# Lcd_CapTouch.net
KiCad netlist of a schematic drawn in Altium Designer
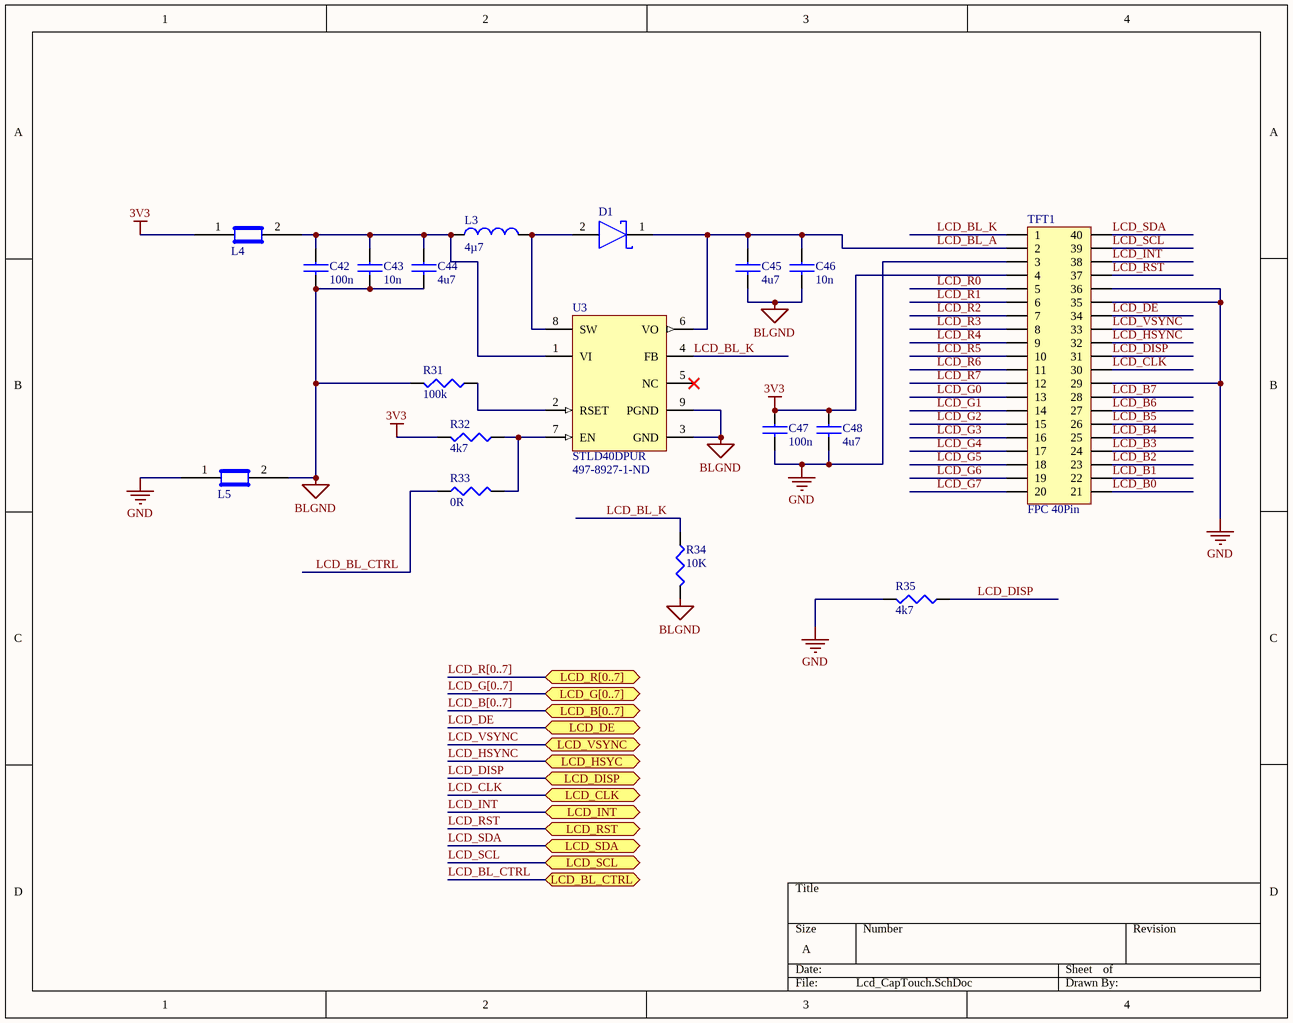
[diagram p0: Lcd_CapTouch.SchDoc]

(export (version "E")
  (design (tool "Eeschema 10.0.6"))
  (components
    (comp (ref "C42")
      (value "100n")
      (footprint "C0402")
      (description "CAP CER .10UF 50V X5R 10% 0402")
      (fields
        (field (name "MANUFACTURER") "TDK Corporation")
        (field (name "MANUFACTURER PART NUMBER") "C1005X5R1H104K")
      )
      (libsource (lib "iMX6_Rex_Development_Baseboard_V1I1") (part "C1005X5R1H104K"))
    )
    (comp (ref "C43")
      (value "10n")
      (footprint "C0402")
      (description "CAP CER 10000PF 16V X7R 10% 0402")
      (fields
        (field (name "MANUFACTURER") "TDK Corporation")
        (field (name "MANUFACTURER PART NUMBER") "C1005X7R1C103K")
      )
      (libsource (lib "iMX6_Rex_Development_Baseboard_V1I1") (part "C1005X7R1C103K"))
    )
    (comp (ref "C44")
      (value "4u7")
      (footprint "C0402")
      (description "CAP CER 4.7UF 10V 20% X5R 0402")
      (fields
        (field (name "MANUFACTURER") "TDK Corporation")
        (field (name "MANUFACTURER PART NUMBER") "C1005X5R1A475M")
        (field (name ".CHECKED PCB") "RF")
        (field (name ".CHECKED SCH") "RF")
      )
      (libsource (lib "iMX6_Rex_Development_Baseboard_V1I1") (part "C1005X5R1A475M"))
    )
    (comp (ref "C45")
      (value "4u7")
      (footprint "C0402")
      (description "CAP CER 4.7UF 10V 20% X5R 0402")
      (fields
        (field (name "MANUFACTURER") "TDK Corporation")
        (field (name "MANUFACTURER PART NUMBER") "C1005X5R1A475M")
        (field (name ".CHECKED PCB") "RF")
        (field (name ".CHECKED SCH") "RF")
      )
      (libsource (lib "iMX6_Rex_Development_Baseboard_V1I1") (part "C1005X5R1A475M"))
    )
    (comp (ref "C46")
      (value "10n")
      (footprint "C0402")
      (description "CAP CER 10000PF 16V X7R 10% 0402")
      (fields
        (field (name "MANUFACTURER") "TDK Corporation")
        (field (name "MANUFACTURER PART NUMBER") "C1005X7R1C103K")
      )
      (libsource (lib "iMX6_Rex_Development_Baseboard_V1I1") (part "C1005X7R1C103K"))
    )
    (comp (ref "C47")
      (value "100n")
      (footprint "C0402")
      (description "CAP CER .10UF 50V X5R 10% 0402")
      (fields
        (field (name "MANUFACTURER") "TDK Corporation")
        (field (name "MANUFACTURER PART NUMBER") "C1005X5R1H104K")
      )
      (libsource (lib "iMX6_Rex_Development_Baseboard_V1I1") (part "C1005X5R1H104K"))
    )
    (comp (ref "C48")
      (value "4u7")
      (footprint "C0402")
      (description "CAP CER 4.7UF 10V 20% X5R 0402")
      (fields
        (field (name "MANUFACTURER") "TDK Corporation")
        (field (name "MANUFACTURER PART NUMBER") "C1005X5R1A475M")
        (field (name ".CHECKED PCB") "RF")
        (field (name ".CHECKED SCH") "RF")
      )
      (libsource (lib "iMX6_Rex_Development_Baseboard_V1I1") (part "C1005X5R1A475M"))
    )
    (comp (ref "D1")
      (value "STPS1L40M")
      (footprint "STPS1L40M")
      (libsource (lib "STLD40DPUR") (part "STPS1L40M"))
    )
    (comp (ref "L3")
      (value "4µ7")
      (footprint "IHLP_255MILx270MIL")
      (description "INDUCTOR POWER 4.7UH 5.5A SMD")
      (fields
        (field (name "MANUFACTURER") "Vishay/Dale")
        (field (name "MANUFACTURER PART NUMBER") "IHLP2525CZER4R7M01")
      )
      (libsource (lib "iMX6_Rex_Development_Baseboard_V1I1") (part "IHLP2525CZER4R7M01"))
    )
    (comp (ref "L4")
      (value "MPZ1608S601A 600OHM/1A")
      (footprint "C0603")
      (description "FERRITE CHIP BEAD 600 OHM SMD 1A")
      (fields
        (field (name "MANUFACTURER") "TDK Corporation")
        (field (name "MANUFACTURER PART NUMBER") "MPZ1608S601A")
        (field (name ".CHECKED PCB") "RF")
        (field (name ".CHECKED SCH") "RF")
      )
      (libsource (lib "iMX6_Rex_Development_Baseboard_V1I1") (part "MPZ1608S601A"))
    )
    (comp (ref "L5")
      (value "MPZ1608S601A 600OHM/1A")
      (footprint "C0603")
      (description "FERRITE CHIP BEAD 600 OHM SMD 1A")
      (fields
        (field (name "MANUFACTURER") "TDK Corporation")
        (field (name "MANUFACTURER PART NUMBER") "MPZ1608S601A")
        (field (name ".CHECKED PCB") "RF")
        (field (name ".CHECKED SCH") "RF")
      )
      (libsource (lib "iMX6_Rex_Development_Baseboard_V1I1") (part "MPZ1608S601A"))
    )
    (comp (ref "R31")
      (value "100k")
      (footprint "R0402")
      (description "RES 10.0K OHM 1/16W 1% 0402 SMD")
      (fields
        (field (name "MANUFACTURER") "Yageo")
        (field (name "MANUFACTURER PART NUMBER") "RC0402FR-0710KL")
      )
      (libsource (lib "iMX6_Rex_Development_Baseboard_V1I1") (part "RC0402FR-0710KL"))
    )
    (comp (ref "R32")
      (value "4k7")
      (footprint "R0402")
      (description "RES 10.0K OHM 1/16W 1% 0402 SMD")
      (fields
        (field (name "MANUFACTURER") "Yageo")
        (field (name "MANUFACTURER PART NUMBER") "RC0402FR-0710KL")
      )
      (libsource (lib "iMX6_Rex_Development_Baseboard_V1I1") (part "RC0402FR-0710KL"))
    )
    (comp (ref "R33")
      (value "0R")
      (footprint "R0402")
      (description "RES 330 OHM 1/16W 1% 0402 SMD")
      (fields
        (field (name "MANUFACTURER") "Vishay Dale")
        (field (name "MANUFACTURER PART NUMBER") "CRCW0402330RFKED")
        (field (name ".CHECKED PCB") "RF")
        (field (name ".CHECKED SCH") "RF")
      )
      (libsource (lib "iMX6_Rex_Development_Baseboard_V1I1") (part "CRCW0402330RFKED"))
    )
    (comp (ref "R34")
      (value "10K")
      (footprint "R0402")
      (description "RES 100 OHM 1/16W 1% 0402 SMD")
      (fields
        (field (name "MANUFACTURER") "Yageo")
        (field (name "MANUFACTURER PART NUMBER") "RC0402FR-07100RL")
        (field (name ".CHECKED PCB") "RF")
        (field (name ".CHECKED SCH") "RF")
      )
      (libsource (lib "iMX6_Rex_Development_Baseboard_V1I1") (part "RC0402FR-07100RL"))
    )
    (comp (ref "R35")
      (value "4k7")
      (footprint "R0402")
      (description "RES 10.0K OHM 1/16W 1% 0402 SMD")
      (fields
        (field (name "MANUFACTURER") "Yageo")
        (field (name "MANUFACTURER PART NUMBER") "RC0402FR-0710KL")
      )
      (libsource (lib "iMX6_Rex_Development_Baseboard_V1I1") (part "RC0402FR-0710KL"))
    )
    (comp (ref "TFT1") (value "FPC 40Pin") (footprint "FPC_40Pin") (libsource (lib "L1") (part "FPC_40Pin")))
    (comp (ref "U3")
      (value "STLD40DPUR")
      (footprint "QFN8_V")
      (description "White Led Power Supply For Large Display Backlight, 8-Pin VFDFPN, Tape and Reel")
      (fields (field (name "SUPPLIER PART NUMBER 1") "497-8927-1-ND"))
      (libsource (lib "STLD40DPUR") (part "STLD40DPUR"))
    )
  )
  (nets
    (net (code "1") (name "/LCD_B0") (class "Default")
      (node (ref "TFT1") (pin "21") (pinfunction "21_21") (pintype "passive"))
    )
    (net (code "2") (name "/LCD_B1") (class "Default")
      (node (ref "TFT1") (pin "22") (pinfunction "22_22") (pintype "passive"))
    )
    (net (code "3") (name "/LCD_B2") (class "Default")
      (node (ref "TFT1") (pin "23") (pinfunction "23_23") (pintype "passive"))
    )
    (net (code "4") (name "/LCD_B3") (class "Default")
      (node (ref "TFT1") (pin "24") (pinfunction "24_24") (pintype "passive"))
    )
    (net (code "5") (name "/LCD_B4") (class "Default")
      (node (ref "TFT1") (pin "25") (pinfunction "25_25") (pintype "passive"))
    )
    (net (code "6") (name "/LCD_B5") (class "Default")
      (node (ref "TFT1") (pin "26") (pinfunction "26_26") (pintype "passive"))
    )
    (net (code "7") (name "/LCD_B6") (class "Default")
      (node (ref "TFT1") (pin "27") (pinfunction "27_27") (pintype "passive"))
    )
    (net (code "8") (name "/LCD_B7") (class "Default")
      (node (ref "TFT1") (pin "28") (pinfunction "28_28") (pintype "passive"))
    )
    (net (code "9") (name "/LCD_BL_A") (class "Default")
      (node (ref "C45") (pin "1") (pinfunction "1_1") (pintype "passive"))
      (node (ref "C46") (pin "1") (pinfunction "1_1") (pintype "passive"))
      (node (ref "D1") (pin "1") (pinfunction "K_1") (pintype "passive"))
      (node (ref "TFT1") (pin "2") (pinfunction "2_2") (pintype "passive"))
      (node (ref "U3") (pin "6") (pinfunction "VO_6") (pintype "output"))
    )
    (net (code "10") (name "/LCD_BL_CTRL") (class "Default")
      (node (ref "R33") (pin "1") (pinfunction "1_1") (pintype "passive"))
    )
    (net (code "11") (name "/LCD_BL_K") (class "Default")
      (node (ref "R34") (pin "1") (pinfunction "1_1") (pintype "passive"))
      (node (ref "TFT1") (pin "1") (pinfunction "1_1") (pintype "passive"))
      (node (ref "U3") (pin "4") (pinfunction "FB_4") (pintype "passive"))
    )
    (net (code "13") (name "/LCD_CLK") (class "Default")
      (node (ref "TFT1") (pin "30") (pinfunction "30_30") (pintype "passive"))
    )
    (net (code "14") (name "/LCD_DE") (class "Default")
      (node (ref "TFT1") (pin "34") (pinfunction "34_34") (pintype "passive"))
    )
    (net (code "15") (name "/LCD_DISP") (class "Default")
      (node (ref "R35") (pin "1") (pinfunction "1_1") (pintype "passive"))
      (node (ref "TFT1") (pin "31") (pinfunction "31_31") (pintype "passive"))
    )
    (net (code "16") (name "/LCD_G0") (class "Default")
      (node (ref "TFT1") (pin "13") (pinfunction "13_13") (pintype "passive"))
    )
    (net (code "17") (name "/LCD_G1") (class "Default")
      (node (ref "TFT1") (pin "14") (pinfunction "14_14") (pintype "passive"))
    )
    (net (code "18") (name "/LCD_G2") (class "Default")
      (node (ref "TFT1") (pin "15") (pinfunction "15_15") (pintype "passive"))
    )
    (net (code "19") (name "/LCD_G3") (class "Default")
      (node (ref "TFT1") (pin "16") (pinfunction "16_16") (pintype "passive"))
    )
    (net (code "20") (name "/LCD_G4") (class "Default")
      (node (ref "TFT1") (pin "17") (pinfunction "17_17") (pintype "passive"))
    )
    (net (code "21") (name "/LCD_G5") (class "Default")
      (node (ref "TFT1") (pin "18") (pinfunction "18_18") (pintype "passive"))
    )
    (net (code "22") (name "/LCD_G6") (class "Default")
      (node (ref "TFT1") (pin "19") (pinfunction "19_19") (pintype "passive"))
    )
    (net (code "23") (name "/LCD_G7") (class "Default")
      (node (ref "TFT1") (pin "20") (pinfunction "20_20") (pintype "passive"))
    )
    (net (code "25") (name "/LCD_HSYNC") (class "Default")
      (node (ref "TFT1") (pin "32") (pinfunction "32_32") (pintype "passive"))
    )
    (net (code "26") (name "/LCD_INT") (class "Default")
      (node (ref "TFT1") (pin "38") (pinfunction "38_38") (pintype "passive"))
    )
    (net (code "27") (name "/LCD_R0") (class "Default")
      (node (ref "TFT1") (pin "5") (pinfunction "5_5") (pintype "passive"))
    )
    (net (code "28") (name "/LCD_R1") (class "Default")
      (node (ref "TFT1") (pin "6") (pinfunction "6_6") (pintype "passive"))
    )
    (net (code "29") (name "/LCD_R2") (class "Default")
      (node (ref "TFT1") (pin "7") (pinfunction "7_7") (pintype "passive"))
    )
    (net (code "30") (name "/LCD_R3") (class "Default")
      (node (ref "TFT1") (pin "8") (pinfunction "8_8") (pintype "passive"))
    )
    (net (code "31") (name "/LCD_R4") (class "Default")
      (node (ref "TFT1") (pin "9") (pinfunction "9_9") (pintype "passive"))
    )
    (net (code "32") (name "/LCD_R5") (class "Default")
      (node (ref "TFT1") (pin "10") (pinfunction "10_10") (pintype "passive"))
    )
    (net (code "33") (name "/LCD_R6") (class "Default")
      (node (ref "TFT1") (pin "11") (pinfunction "11_11") (pintype "passive"))
    )
    (net (code "34") (name "/LCD_R7") (class "Default")
      (node (ref "TFT1") (pin "12") (pinfunction "12_12") (pintype "passive"))
    )
    (net (code "35") (name "/LCD_RST") (class "Default")
      (node (ref "TFT1") (pin "37") (pinfunction "37_37") (pintype "passive"))
    )
    (net (code "37") (name "/LCD_SCL") (class "Default")
      (node (ref "TFT1") (pin "39") (pinfunction "39_39") (pintype "passive"))
    )
    (net (code "38") (name "/LCD_SDA") (class "Default")
      (node (ref "TFT1") (pin "40") (pinfunction "40_40") (pintype "passive"))
    )
    (net (code "39") (name "/LCD_VSYNC") (class "Default")
      (node (ref "TFT1") (pin "33") (pinfunction "33_33") (pintype "passive"))
    )
    (net (code "40") (name "3V3") (class "Default")
      (node (ref "C47") (pin "1") (pinfunction "1_1") (pintype "passive"))
      (node (ref "C48") (pin "1") (pinfunction "1_1") (pintype "passive"))
      (node (ref "L4") (pin "1") (pinfunction "1_1") (pintype "passive"))
      (node (ref "R32") (pin "2") (pinfunction "2_2") (pintype "passive"))
      (node (ref "TFT1") (pin "4") (pinfunction "4_4") (pintype "passive"))
    )
    (net (code "41") (name "BLGND") (class "Default")
      (node (ref "C42") (pin "2") (pinfunction "2_2") (pintype "passive"))
      (node (ref "C43") (pin "2") (pinfunction "2_2") (pintype "passive"))
      (node (ref "C44") (pin "2") (pinfunction "2_2") (pintype "passive"))
      (node (ref "C45") (pin "2") (pinfunction "2_2") (pintype "passive"))
      (node (ref "C46") (pin "2") (pinfunction "2_2") (pintype "passive"))
      (node (ref "L5") (pin "2") (pinfunction "2_2") (pintype "passive"))
      (node (ref "R31") (pin "2") (pinfunction "2_2") (pintype "passive"))
      (node (ref "R34") (pin "2") (pinfunction "2_2") (pintype "passive"))
      (node (ref "U3") (pin "3") (pinfunction "GND_3") (pintype "power_in"))
      (node (ref "U3") (pin "9") (pinfunction "PGND_9") (pintype "power_in"))
    )
    (net (code "42") (name "GND") (class "Default")
      (node (ref "C47") (pin "2") (pinfunction "2_2") (pintype "passive"))
      (node (ref "C48") (pin "2") (pinfunction "2_2") (pintype "passive"))
      (node (ref "L5") (pin "1") (pinfunction "1_1") (pintype "passive"))
      (node (ref "R35") (pin "2") (pinfunction "2_2") (pintype "passive"))
      (node (ref "TFT1") (pin "29") (pinfunction "29_29") (pintype "passive"))
      (node (ref "TFT1") (pin "3") (pinfunction "3_3") (pintype "passive"))
      (node (ref "TFT1") (pin "35") (pinfunction "35_35") (pintype "passive"))
      (node (ref "TFT1") (pin "36") (pinfunction "36_36") (pintype "passive"))
    )
    (net (code "43") (name "Net-(D1-A)") (class "Default")
      (node (ref "D1") (pin "2") (pinfunction "A_2") (pintype "passive"))
      (node (ref "L3") (pin "2") (pinfunction "2_2") (pintype "passive"))
      (node (ref "U3") (pin "8") (pinfunction "SW_8") (pintype "open_collector"))
    )
    (net (code "44") (name "Net-(U3-EN)") (class "Default")
      (node (ref "R32") (pin "1") (pinfunction "1_1") (pintype "passive"))
      (node (ref "R33") (pin "2") (pinfunction "2_2") (pintype "passive"))
      (node (ref "U3") (pin "7") (pinfunction "EN_7") (pintype "input"))
    )
    (net (code "45") (name "Net-(U3-RSET)") (class "Default")
      (node (ref "R31") (pin "1") (pinfunction "1_1") (pintype "passive"))
      (node (ref "U3") (pin "2") (pinfunction "RSET_2") (pintype "input"))
    )
    (net (code "46") (name "Net-(U3-VI)") (class "Default")
      (node (ref "C42") (pin "1") (pinfunction "1_1") (pintype "passive"))
      (node (ref "C43") (pin "1") (pinfunction "1_1") (pintype "passive"))
      (node (ref "C44") (pin "1") (pinfunction "1_1") (pintype "passive"))
      (node (ref "L3") (pin "1") (pinfunction "1_1") (pintype "passive"))
      (node (ref "L4") (pin "2") (pinfunction "2_2") (pintype "passive"))
      (node (ref "U3") (pin "1") (pinfunction "VI_1") (pintype "power_in"))
    )
    (net (code "47") (name "unconnected-(U3-NC-Pad5)") (class "Default")
      (node (ref "U3") (pin "5") (pinfunction "NC_5") (pintype "passive+no_connect"))
    )
  )
)
